# energy_monitor_v1.net
KiCad netlist of a schematic drawn in EAGLE
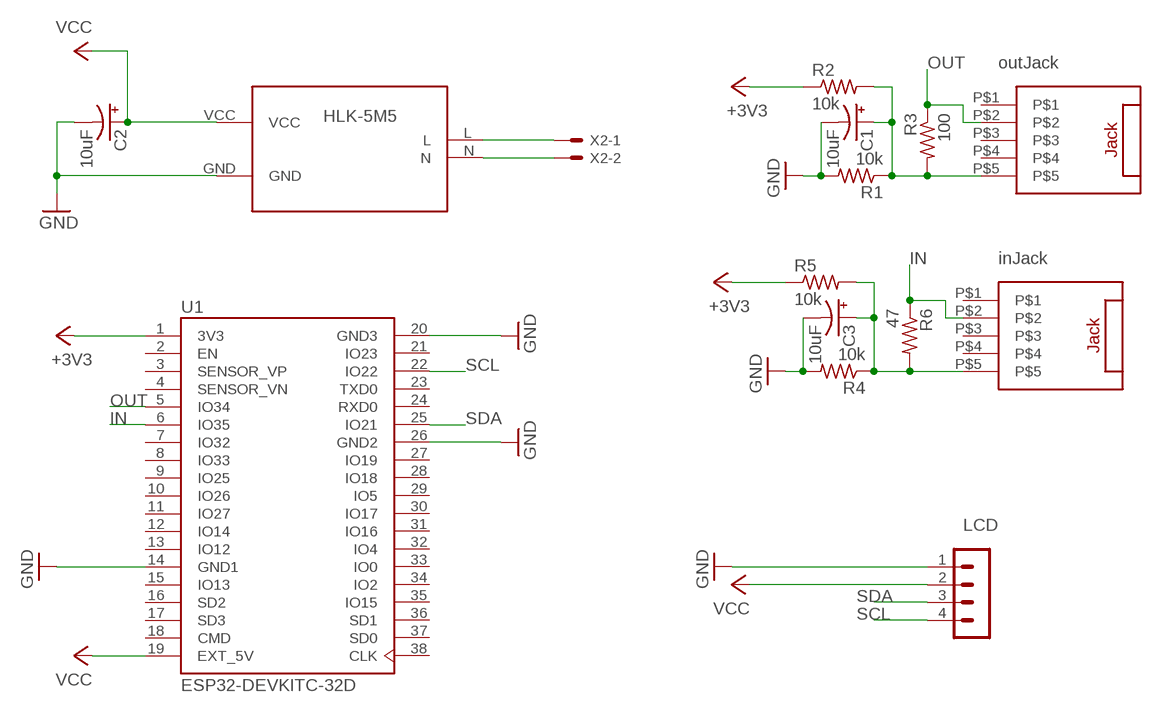
[diagram p0: schematic, sheet 1]

(export (version "E")
  (design (tool "Eeschema 10.0.6"))
  (components
    (comp (ref "C1")
      (value "10uF")
      (footprint "eagle-import:B45181A")
      (libsource (lib "eagle-import") (part "CPOL-USB45181A"))
    )
    (comp (ref "C2")
      (value "10uF")
      (footprint "eagle-import:B45181A")
      (libsource (lib "eagle-import") (part "CPOL-USB45181A"))
    )
    (comp (ref "C3")
      (value "10uF")
      (footprint "eagle-import:B45181A")
      (libsource (lib "eagle-import") (part "CPOL-USB45181A"))
    )
    (comp (ref "HLK-5M5")
      (value "HLK-5M05")
      (footprint "eagle-import:CONV_HLK-5M05")
      (libsource (lib "eagle-import") (part "HLK-5M05"))
    )
    (comp (ref "R1")
      (value "10k")
      (footprint "eagle-import:0204_7")
      (libsource (lib "eagle-import") (part "R-US_0204/7"))
    )
    (comp (ref "R2")
      (value "10k")
      (footprint "eagle-import:0204_7")
      (libsource (lib "eagle-import") (part "R-US_0204/7"))
    )
    (comp (ref "R3")
      (value "100")
      (footprint "eagle-import:0204_7")
      (libsource (lib "eagle-import") (part "R-US_0204/7"))
    )
    (comp (ref "R4")
      (value "10k")
      (footprint "eagle-import:0204_7")
      (libsource (lib "eagle-import") (part "R-US_0204/7"))
    )
    (comp (ref "R5")
      (value "10k")
      (footprint "eagle-import:0204_7")
      (libsource (lib "eagle-import") (part "R-US_0204/7"))
    )
    (comp (ref "R6")
      (value "47")
      (footprint "eagle-import:0204_7")
      (libsource (lib "eagle-import") (part "R-US_0204/7"))
    )
    (comp (ref "SV3")
      (value "MA04-1")
      (footprint "eagle-import:MA04-1")
      (libsource (lib "eagle-import") (part "MA04-1"))
    )
    (comp (ref "U$1")
      (value "JACK_5PINS")
      (footprint "eagle-import:JACK_5PINS")
      (libsource (lib "eagle-import") (part "JACK_5PINS"))
    )
    (comp (ref "U$2")
      (value "JACK_5PINS")
      (footprint "eagle-import:JACK_5PINS")
      (libsource (lib "eagle-import") (part "JACK_5PINS"))
    )
    (comp (ref "U1")
      (value "ESP32-DEVKITC-32D")
      (footprint "eagle-import:MODULE_ESP32-DEVKITC-32D")
      (fields (field (name "MF") "Espressif Systems"))
      (libsource (lib "eagle-import") (part "ESP32-DEVKITC-32D"))
    )
    (comp (ref "X2")
      (value "JST-XH-02-PIN-LONG-PAD")
      (footprint "eagle-import:JST-XH-02-PACKAGE-LONG-PAD")
      (libsource (lib "eagle-import") (part "JST-XH-02-PIN-LONG-PAD"))
    )
  )
  (nets
    (net (code "1") (name "+3V3") (class "Default")
      (node (ref "R2") (pin "1") (pinfunction "1_1") (pintype "passive"))
      (node (ref "R5") (pin "1") (pinfunction "1_1") (pintype "passive"))
      (node (ref "U1") (pin "1") (pinfunction "3V3_1") (pintype "power_in"))
    )
    (net (code "2") (name "/IN") (class "Default")
      (node (ref "R6") (pin "1") (pinfunction "1_1") (pintype "passive"))
      (node (ref "U$2") (pin "P$2") (pinfunction "P$2_P$2") (pintype "bidirectional"))
      (node (ref "U1") (pin "6") (pinfunction "IO35_6") (pintype "bidirectional"))
    )
    (net (code "3") (name "/OUT") (class "Default")
      (node (ref "R3") (pin "1") (pinfunction "1_1") (pintype "passive"))
      (node (ref "U$1") (pin "P$2") (pinfunction "P$2_P$2") (pintype "bidirectional"))
      (node (ref "U1") (pin "5") (pinfunction "IO34_5") (pintype "bidirectional"))
    )
    (net (code "4") (name "/SCL") (class "Default")
      (node (ref "SV3") (pin "4") (pinfunction "4_4") (pintype "passive"))
      (node (ref "U1") (pin "22") (pinfunction "IO22_22") (pintype "bidirectional"))
    )
    (net (code "5") (name "/SDA") (class "Default")
      (node (ref "SV3") (pin "3") (pinfunction "3_3") (pintype "passive"))
      (node (ref "U1") (pin "25") (pinfunction "IO21_25") (pintype "bidirectional"))
    )
    (net (code "6") (name "GND") (class "Default")
      (node (ref "C1") (pin "-") (pinfunction "-_-") (pintype "passive"))
      (node (ref "C2") (pin "-") (pinfunction "-_-") (pintype "passive"))
      (node (ref "C3") (pin "-") (pinfunction "-_-") (pintype "passive"))
      (node (ref "HLK-5M5") (pin "GND") (pinfunction "GND_GND") (pintype "bidirectional"))
      (node (ref "R1") (pin "2") (pinfunction "2_2") (pintype "passive"))
      (node (ref "R4") (pin "2") (pinfunction "2_2") (pintype "passive"))
      (node (ref "SV3") (pin "1") (pinfunction "1_1") (pintype "passive"))
      (node (ref "U1") (pin "14") (pinfunction "GND1_14") (pintype "power_in"))
      (node (ref "U1") (pin "20") (pinfunction "GND3_20") (pintype "power_in"))
      (node (ref "U1") (pin "26") (pinfunction "GND2_26") (pintype "power_in"))
    )
    (net (code "7") (name "Net-(C1-Pad+)") (class "Default")
      (node (ref "C1") (pin "+") (pinfunction "+_+") (pintype "passive"))
      (node (ref "R1") (pin "1") (pinfunction "1_1") (pintype "passive"))
      (node (ref "R2") (pin "2") (pinfunction "2_2") (pintype "passive"))
      (node (ref "R3") (pin "2") (pinfunction "2_2") (pintype "passive"))
      (node (ref "U$1") (pin "P$5") (pinfunction "P$5_P$5") (pintype "bidirectional"))
    )
    (net (code "8") (name "Net-(C3-Pad+)") (class "Default")
      (node (ref "C3") (pin "+") (pinfunction "+_+") (pintype "passive"))
      (node (ref "R4") (pin "1") (pinfunction "1_1") (pintype "passive"))
      (node (ref "R5") (pin "2") (pinfunction "2_2") (pintype "passive"))
      (node (ref "R6") (pin "2") (pinfunction "2_2") (pintype "passive"))
      (node (ref "U$2") (pin "P$5") (pinfunction "P$5_P$5") (pintype "bidirectional"))
    )
    (net (code "9") (name "Net-(X2A-S)") (class "Default")
      (node (ref "HLK-5M5") (pin "L") (pinfunction "L_L") (pintype "bidirectional"))
      (node (ref "X2") (pin "1") (pinfunction "S_1") (pintype "passive"))
    )
    (net (code "10") (name "Net-(X2B-S)") (class "Default")
      (node (ref "HLK-5M5") (pin "N") (pinfunction "N_N") (pintype "bidirectional"))
      (node (ref "X2") (pin "2") (pinfunction "S_2") (pintype "passive"))
    )
    (net (code "11") (name "VCC") (class "Default")
      (node (ref "C2") (pin "+") (pinfunction "+_+") (pintype "passive"))
      (node (ref "HLK-5M5") (pin "VCC") (pinfunction "VCC_VCC") (pintype "bidirectional"))
      (node (ref "SV3") (pin "2") (pinfunction "2_2") (pintype "passive"))
      (node (ref "U1") (pin "19") (pinfunction "EXT_5V_19") (pintype "power_in"))
    )
    (net (code "12") (name "unconnected-(U$1-PadP$1)") (class "Default")
      (node (ref "U$1") (pin "P$1") (pinfunction "P$1_P$1") (pintype "bidirectional"))
    )
    (net (code "13") (name "unconnected-(U$1-PadP$3)") (class "Default")
      (node (ref "U$1") (pin "P$3") (pinfunction "P$3_P$3") (pintype "bidirectional"))
    )
    (net (code "14") (name "unconnected-(U$1-PadP$4)") (class "Default")
      (node (ref "U$1") (pin "P$4") (pinfunction "P$4_P$4") (pintype "bidirectional"))
    )
    (net (code "15") (name "unconnected-(U$2-PadP$1)") (class "Default")
      (node (ref "U$2") (pin "P$1") (pinfunction "P$1_P$1") (pintype "bidirectional"))
    )
    (net (code "16") (name "unconnected-(U$2-PadP$3)") (class "Default")
      (node (ref "U$2") (pin "P$3") (pinfunction "P$3_P$3") (pintype "bidirectional"))
    )
    (net (code "17") (name "unconnected-(U$2-PadP$4)") (class "Default")
      (node (ref "U$2") (pin "P$4") (pinfunction "P$4_P$4") (pintype "bidirectional"))
    )
    (net (code "18") (name "unconnected-(U1-CLK-Pad38)") (class "Default")
      (node (ref "U1") (pin "38") (pinfunction "CLK_38") (pintype "input"))
    )
    (net (code "19") (name "unconnected-(U1-CMD-Pad18)") (class "Default")
      (node (ref "U1") (pin "18") (pinfunction "CMD_18") (pintype "bidirectional"))
    )
    (net (code "20") (name "unconnected-(U1-EN-Pad2)") (class "Default")
      (node (ref "U1") (pin "2") (pinfunction "EN_2") (pintype "input"))
    )
    (net (code "21") (name "unconnected-(U1-IO0-Pad33)") (class "Default")
      (node (ref "U1") (pin "33") (pinfunction "IO0_33") (pintype "bidirectional"))
    )
    (net (code "22") (name "unconnected-(U1-IO2-Pad34)") (class "Default")
      (node (ref "U1") (pin "34") (pinfunction "IO2_34") (pintype "bidirectional"))
    )
    (net (code "23") (name "unconnected-(U1-IO4-Pad32)") (class "Default")
      (node (ref "U1") (pin "32") (pinfunction "IO4_32") (pintype "bidirectional"))
    )
    (net (code "24") (name "unconnected-(U1-IO5-Pad29)") (class "Default")
      (node (ref "U1") (pin "29") (pinfunction "IO5_29") (pintype "bidirectional"))
    )
    (net (code "25") (name "unconnected-(U1-IO12-Pad13)") (class "Default")
      (node (ref "U1") (pin "13") (pinfunction "IO12_13") (pintype "bidirectional"))
    )
    (net (code "26") (name "unconnected-(U1-IO13-Pad15)") (class "Default")
      (node (ref "U1") (pin "15") (pinfunction "IO13_15") (pintype "bidirectional"))
    )
    (net (code "27") (name "unconnected-(U1-IO14-Pad12)") (class "Default")
      (node (ref "U1") (pin "12") (pinfunction "IO14_12") (pintype "bidirectional"))
    )
    (net (code "28") (name "unconnected-(U1-IO15-Pad35)") (class "Default")
      (node (ref "U1") (pin "35") (pinfunction "IO15_35") (pintype "bidirectional"))
    )
    (net (code "29") (name "unconnected-(U1-IO16-Pad31)") (class "Default")
      (node (ref "U1") (pin "31") (pinfunction "IO16_31") (pintype "bidirectional"))
    )
    (net (code "30") (name "unconnected-(U1-IO17-Pad30)") (class "Default")
      (node (ref "U1") (pin "30") (pinfunction "IO17_30") (pintype "bidirectional"))
    )
    (net (code "31") (name "unconnected-(U1-IO18-Pad28)") (class "Default")
      (node (ref "U1") (pin "28") (pinfunction "IO18_28") (pintype "bidirectional"))
    )
    (net (code "32") (name "unconnected-(U1-IO19-Pad27)") (class "Default")
      (node (ref "U1") (pin "27") (pinfunction "IO19_27") (pintype "bidirectional"))
    )
    (net (code "33") (name "unconnected-(U1-IO23-Pad21)") (class "Default")
      (node (ref "U1") (pin "21") (pinfunction "IO23_21") (pintype "bidirectional"))
    )
    (net (code "34") (name "unconnected-(U1-IO25-Pad9)") (class "Default")
      (node (ref "U1") (pin "9") (pinfunction "IO25_9") (pintype "bidirectional"))
    )
    (net (code "35") (name "unconnected-(U1-IO26-Pad10)") (class "Default")
      (node (ref "U1") (pin "10") (pinfunction "IO26_10") (pintype "bidirectional"))
    )
    (net (code "36") (name "unconnected-(U1-IO27-Pad11)") (class "Default")
      (node (ref "U1") (pin "11") (pinfunction "IO27_11") (pintype "bidirectional"))
    )
    (net (code "37") (name "unconnected-(U1-IO32-Pad7)") (class "Default")
      (node (ref "U1") (pin "7") (pinfunction "IO32_7") (pintype "bidirectional"))
    )
    (net (code "38") (name "unconnected-(U1-IO33-Pad8)") (class "Default")
      (node (ref "U1") (pin "8") (pinfunction "IO33_8") (pintype "bidirectional"))
    )
    (net (code "39") (name "unconnected-(U1-RXD0-Pad24)") (class "Default")
      (node (ref "U1") (pin "24") (pinfunction "RXD0_24") (pintype "input"))
    )
    (net (code "40") (name "unconnected-(U1-SD0-Pad37)") (class "Default")
      (node (ref "U1") (pin "37") (pinfunction "SD0_37") (pintype "bidirectional"))
    )
    (net (code "41") (name "unconnected-(U1-SD1-Pad36)") (class "Default")
      (node (ref "U1") (pin "36") (pinfunction "SD1_36") (pintype "bidirectional"))
    )
    (net (code "42") (name "unconnected-(U1-SD2-Pad16)") (class "Default")
      (node (ref "U1") (pin "16") (pinfunction "SD2_16") (pintype "bidirectional"))
    )
    (net (code "43") (name "unconnected-(U1-SD3-Pad17)") (class "Default")
      (node (ref "U1") (pin "17") (pinfunction "SD3_17") (pintype "bidirectional"))
    )
    (net (code "44") (name "unconnected-(U1-SENSOR_VN-Pad4)") (class "Default")
      (node (ref "U1") (pin "4") (pinfunction "SENSOR_VN_4") (pintype "input"))
    )
    (net (code "45") (name "unconnected-(U1-SENSOR_VP-Pad3)") (class "Default")
      (node (ref "U1") (pin "3") (pinfunction "SENSOR_VP_3") (pintype "input"))
    )
    (net (code "46") (name "unconnected-(U1-TXD0-Pad23)") (class "Default")
      (node (ref "U1") (pin "23") (pinfunction "TXD0_23") (pintype "output"))
    )
  )
)
